# sGPSDO_MCU_1V0.net
KiCad netlist of a schematic drawn in EAGLE
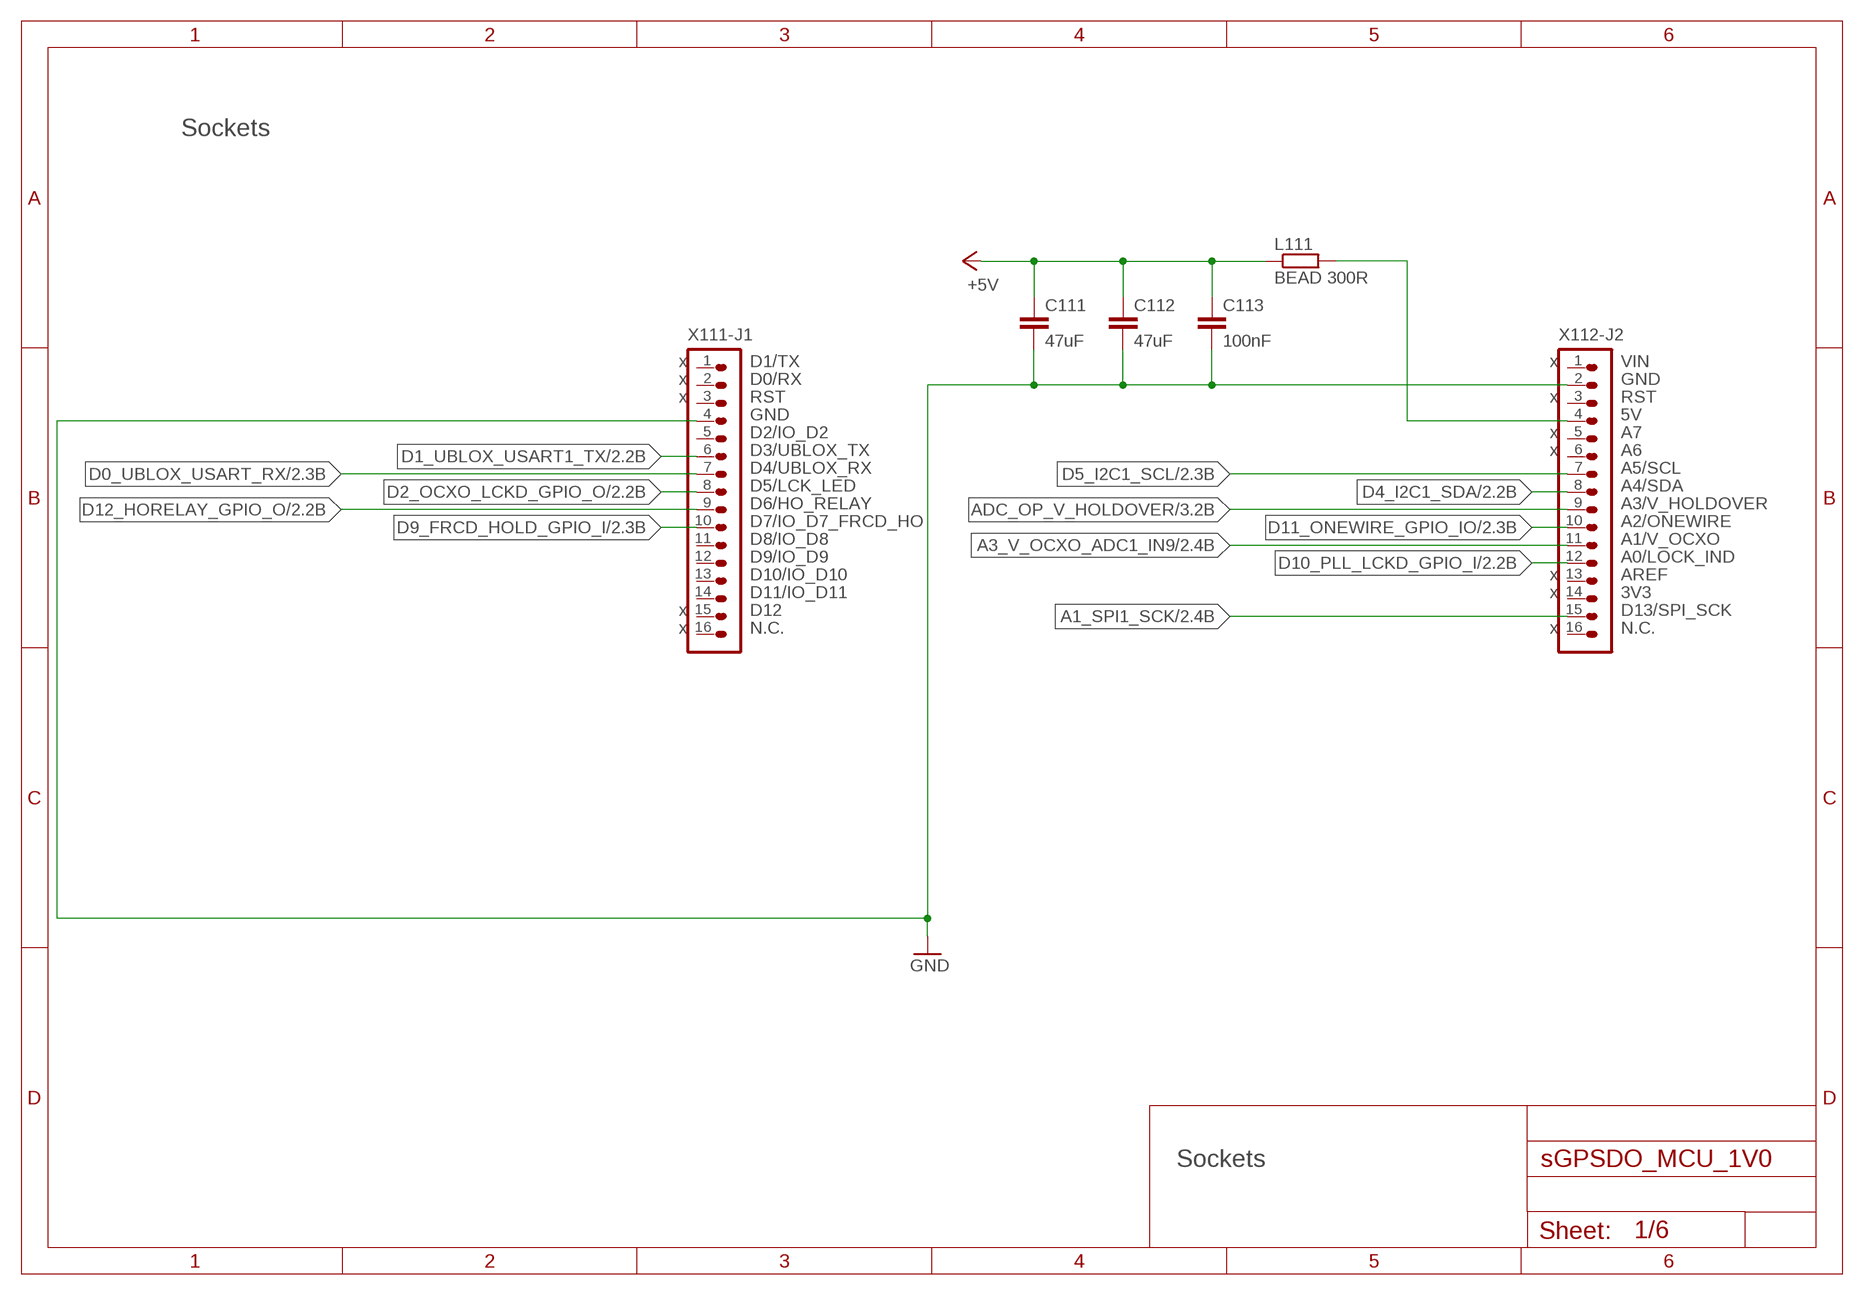
[diagram p0: schematic, sheet 1]
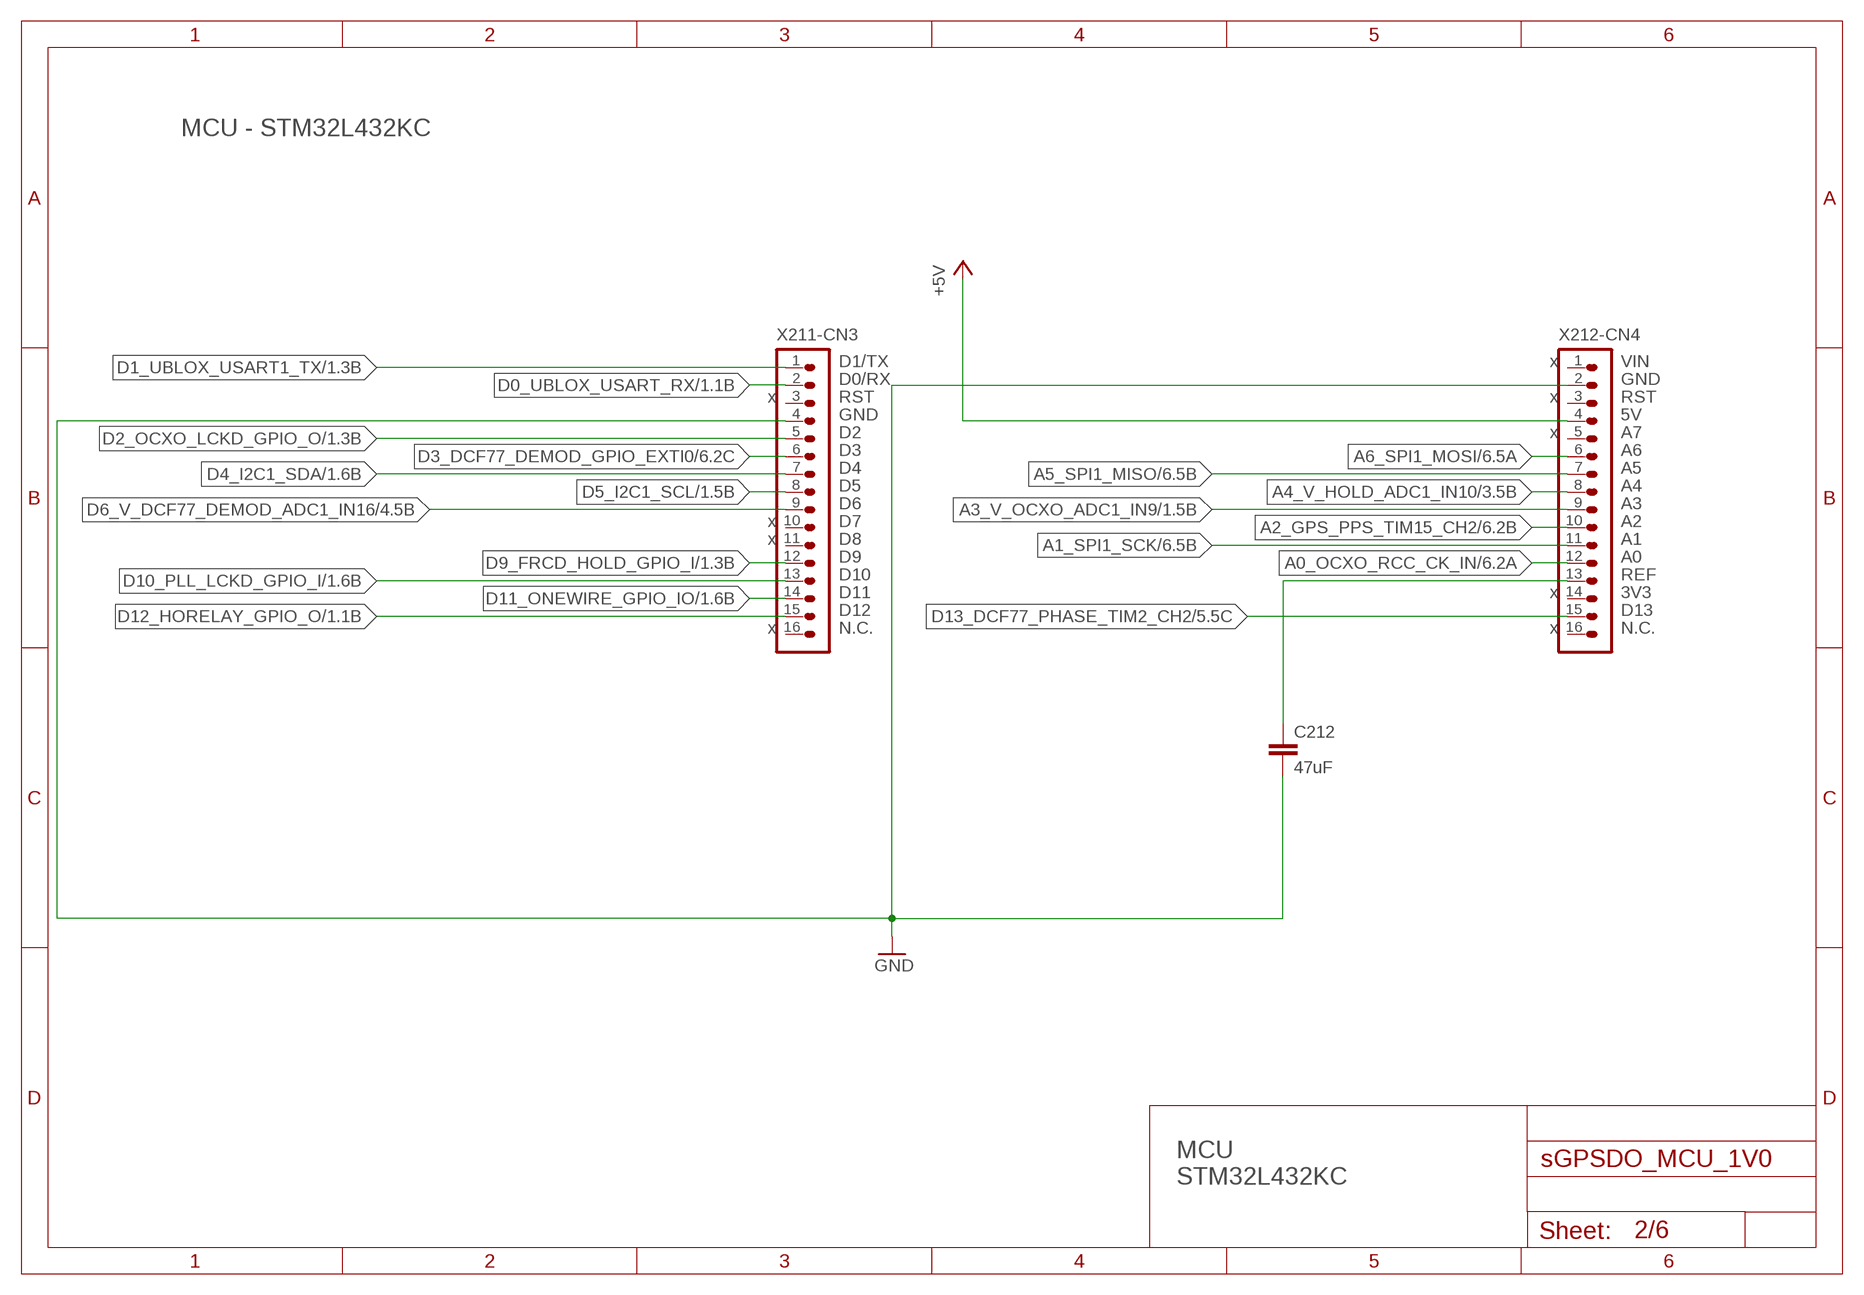
[diagram p1: schematic, sheet 2]
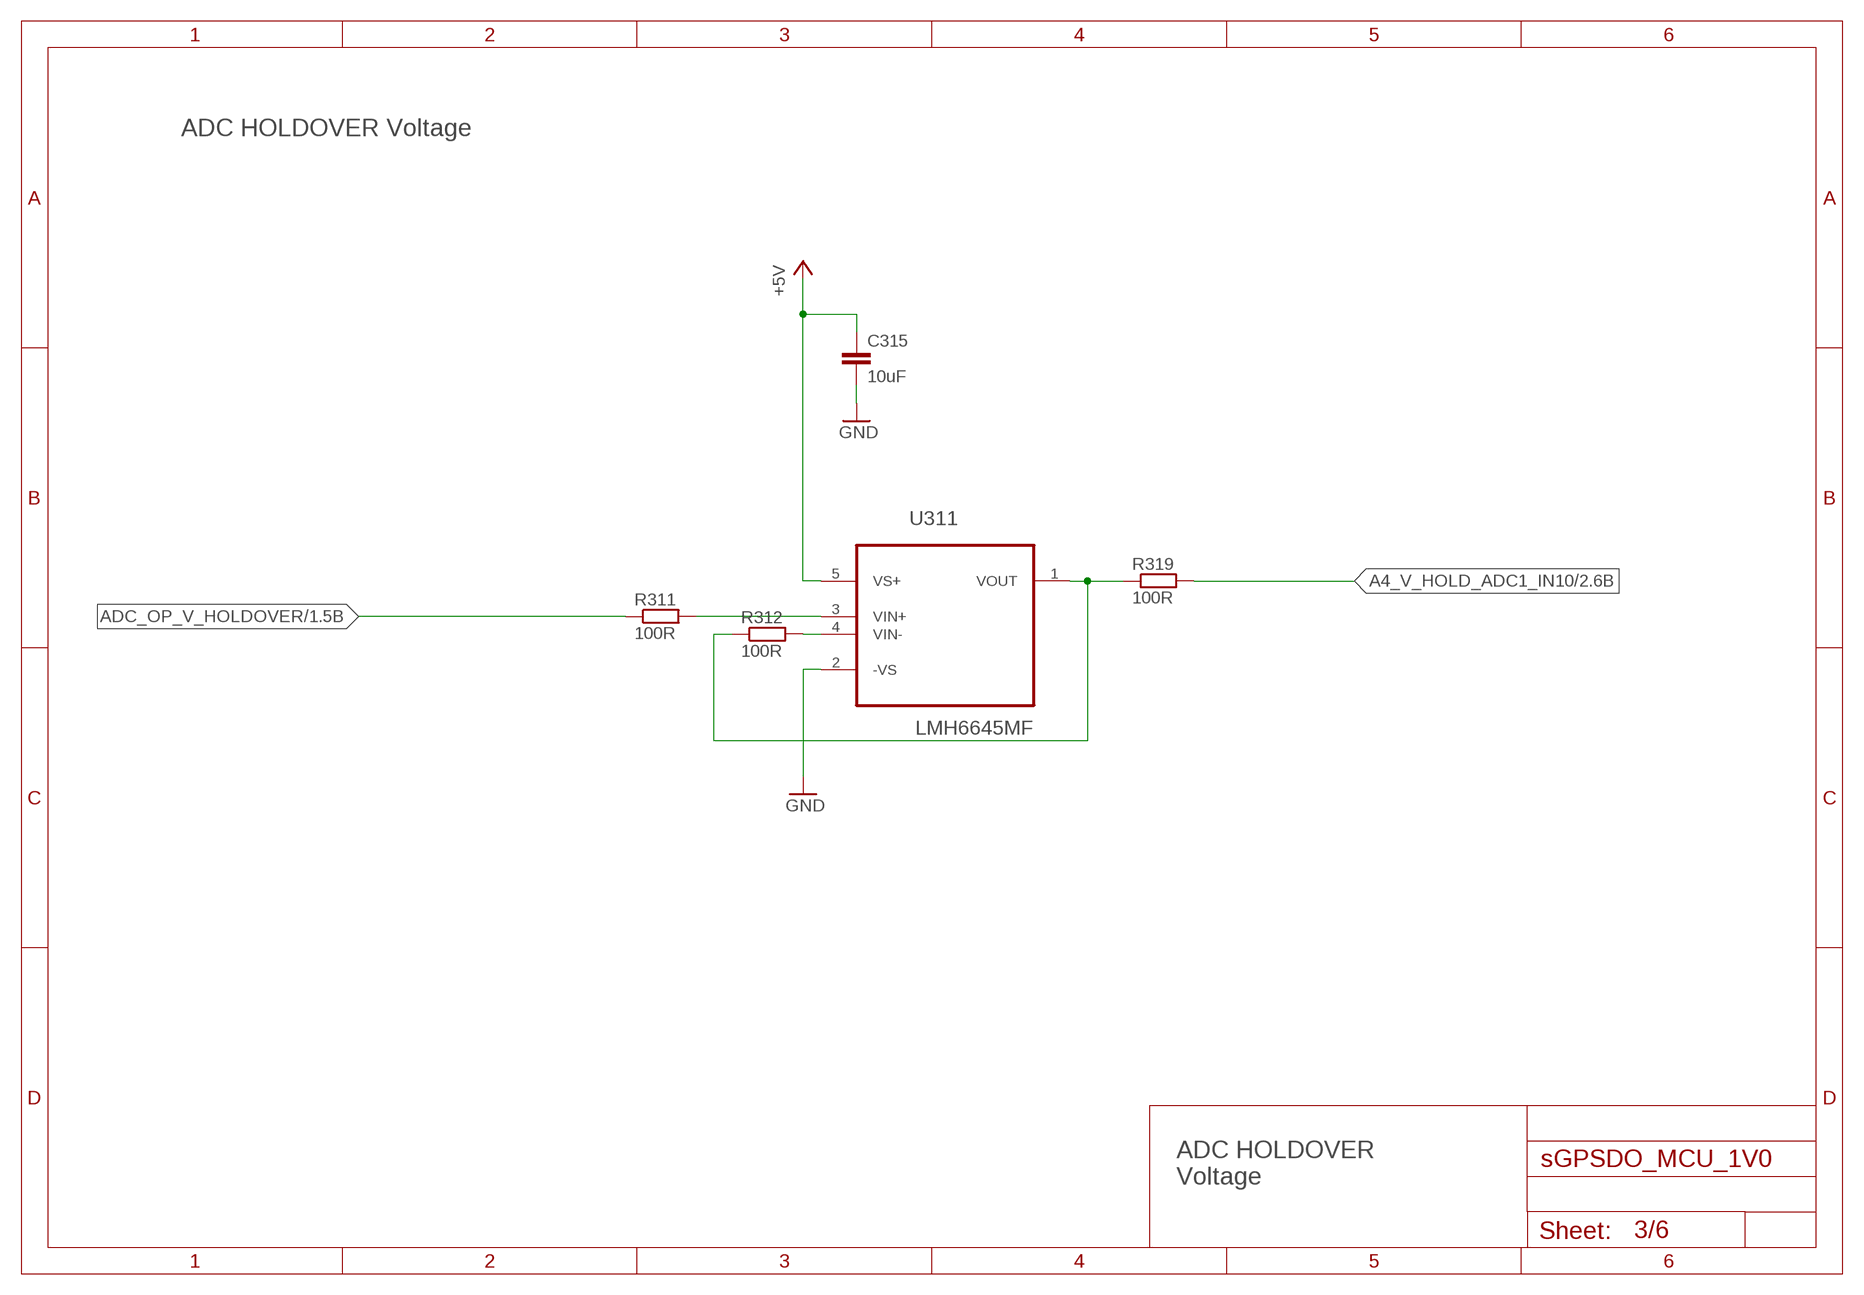
[diagram p2: schematic, sheet 3]
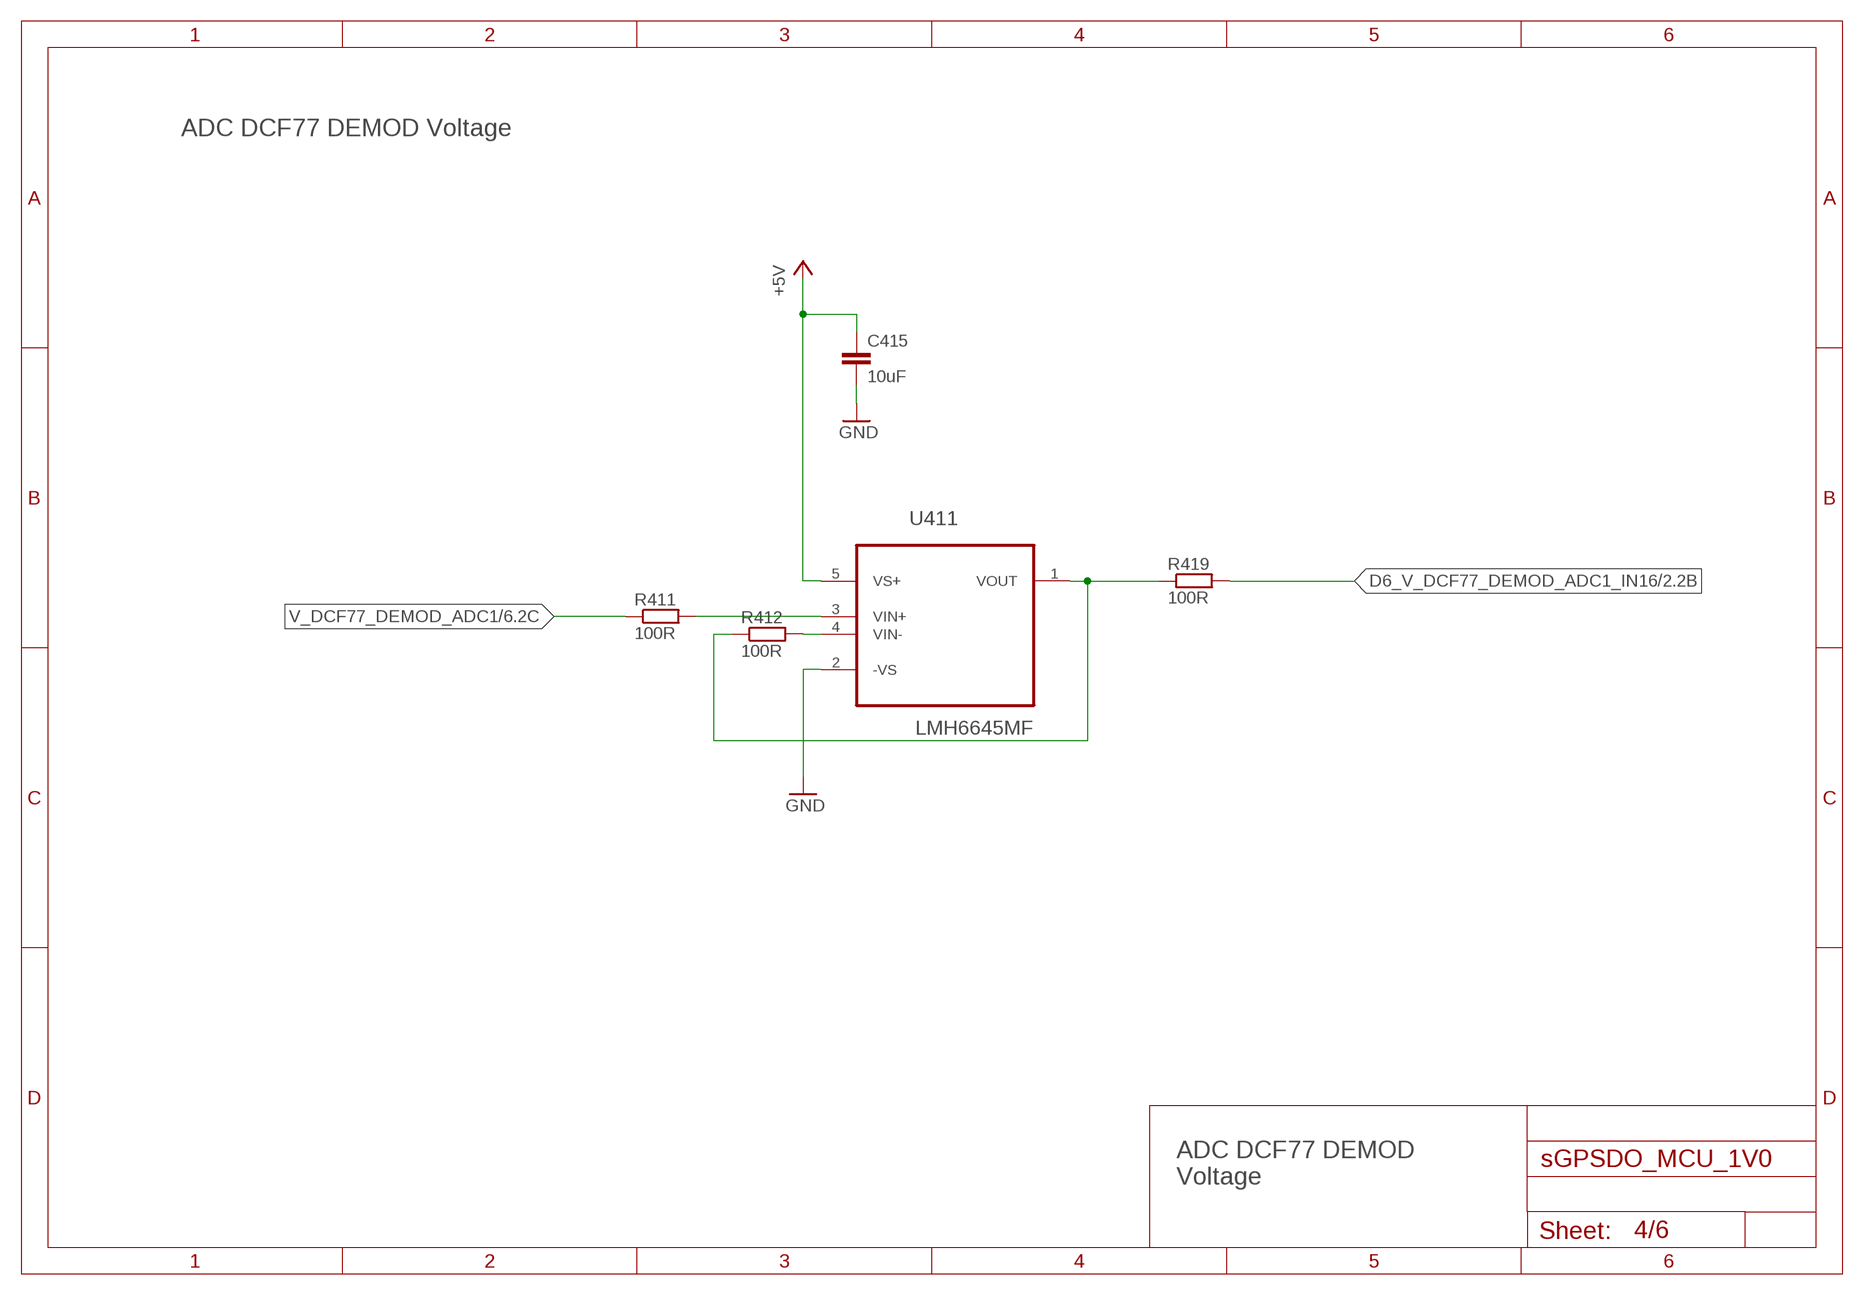
[diagram p3: schematic, sheet 4]
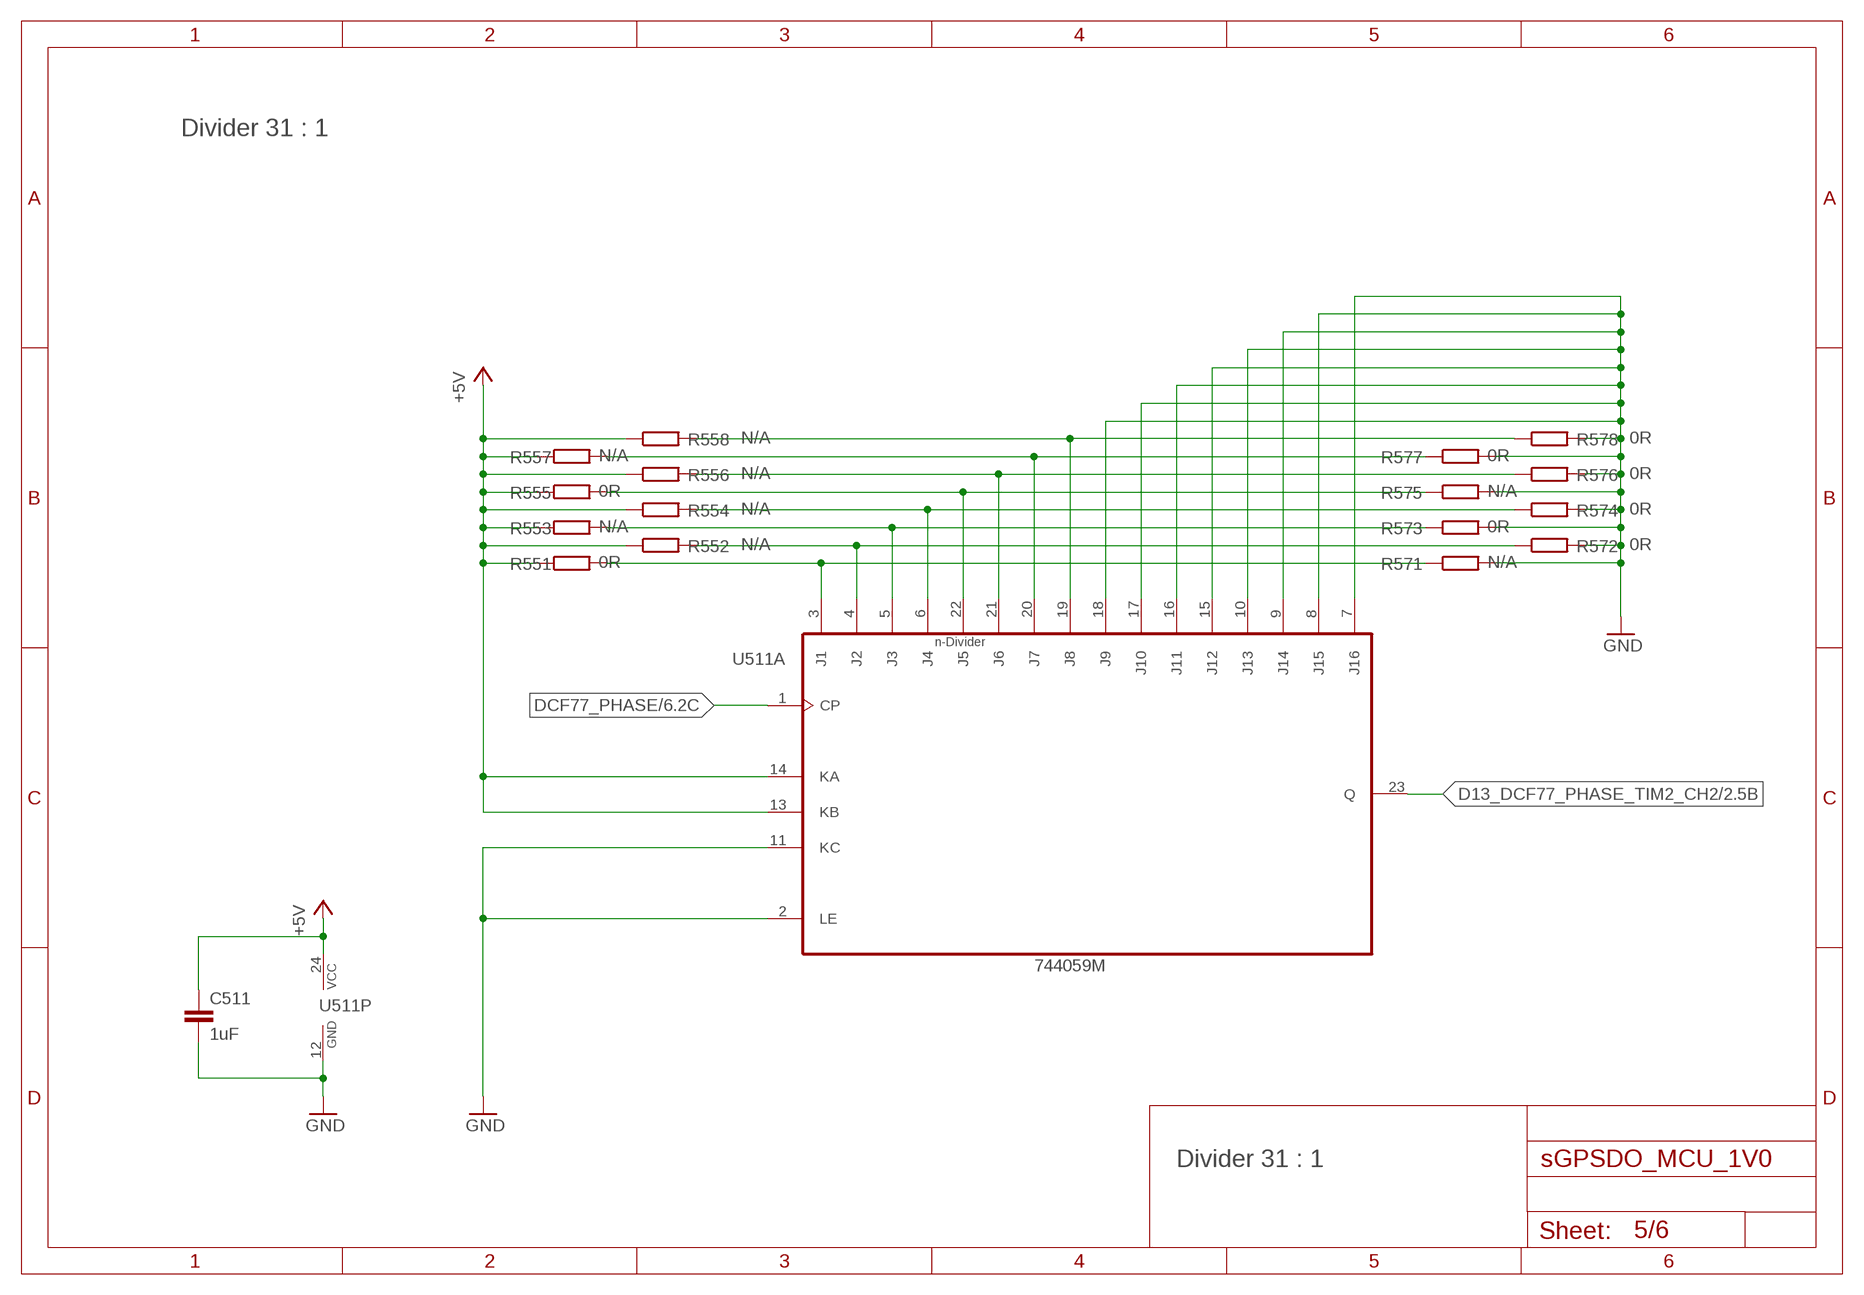
[diagram p4: schematic, sheet 5]
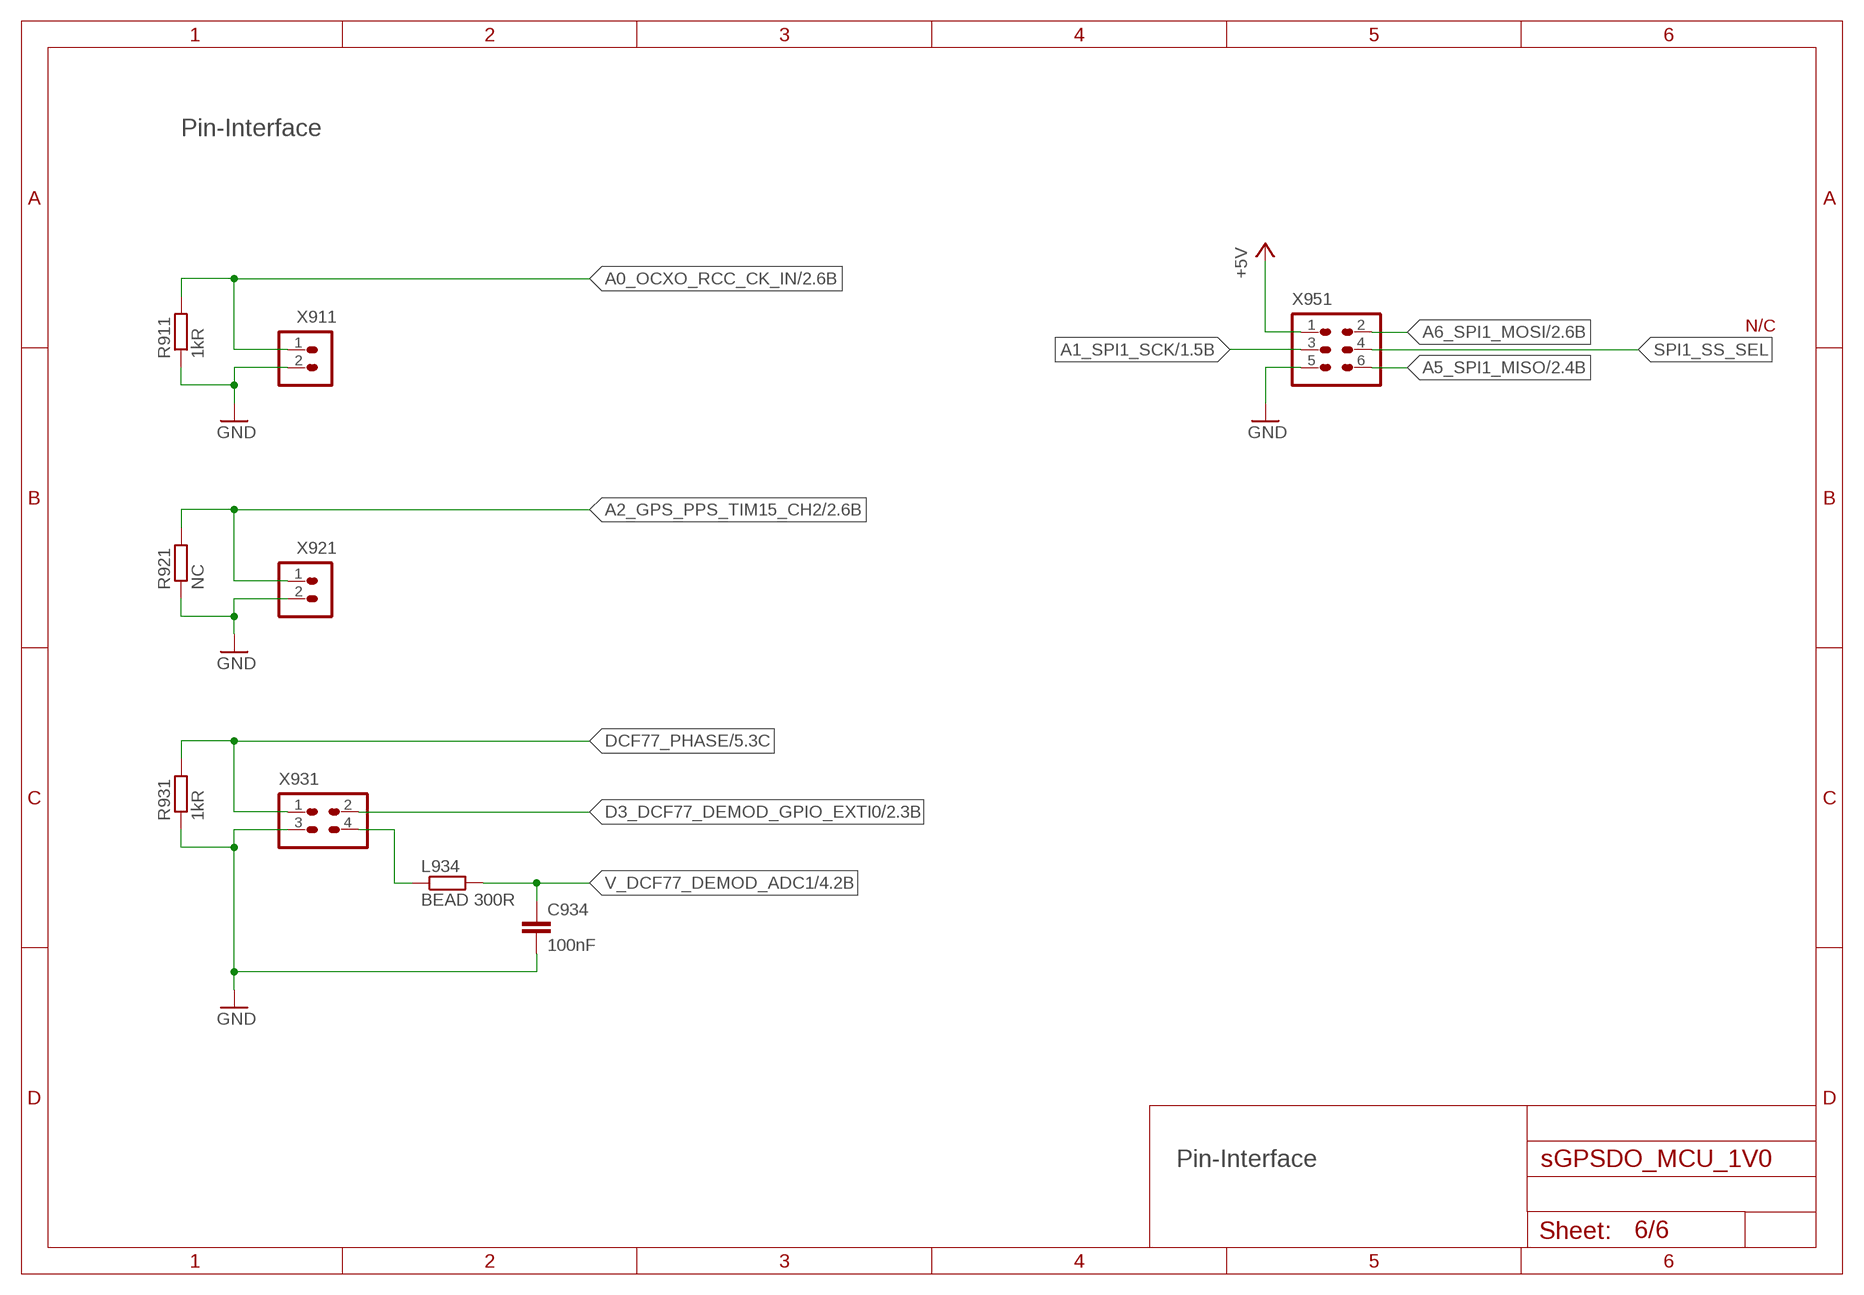
[diagram p5: schematic, sheet 6]

(export (version "E")
  (design (tool "Eeschema 10.0.6"))
  (components
    (comp (ref "C315")
      (value "10uF")
      (footprint "eagle-import:C0805")
      (libsource (lib "eagle-import") (part "C-EUC0805"))
    )
    (comp (ref "R311")
      (value "100R")
      (footprint "eagle-import:R0805")
      (libsource (lib "eagle-import") (part "R-EU_R0805"))
    )
    (comp (ref "R312")
      (value "100R")
      (footprint "eagle-import:R0805")
      (libsource (lib "eagle-import") (part "R-EU_R0805"))
    )
    (comp (ref "R319")
      (value "100R")
      (footprint "eagle-import:R0805")
      (libsource (lib "eagle-import") (part "R-EU_R0805"))
    )
    (comp (ref "U311")
      (value "LMH6645MF")
      (footprint "eagle-import:SOT-23-5")
      (libsource (lib "eagle-import") (part "LMH6645MF"))
    )
    (comp (ref "C511")
      (value "1uF")
      (footprint "eagle-import:C0805")
      (libsource (lib "eagle-import") (part "C-EUC0805"))
    )
    (comp (ref "R551")
      (value "0R")
      (footprint "eagle-import:R0402")
      (libsource (lib "eagle-import") (part "R-EU_R0402"))
    )
    (comp (ref "R552")
      (value "N/A")
      (footprint "eagle-import:R0402")
      (libsource (lib "eagle-import") (part "R-EU_R0402"))
    )
    (comp (ref "R553")
      (value "N/A")
      (footprint "eagle-import:R0402")
      (libsource (lib "eagle-import") (part "R-EU_R0402"))
    )
    (comp (ref "R554")
      (value "N/A")
      (footprint "eagle-import:R0402")
      (libsource (lib "eagle-import") (part "R-EU_R0402"))
    )
    (comp (ref "R555")
      (value "0R")
      (footprint "eagle-import:R0402")
      (libsource (lib "eagle-import") (part "R-EU_R0402"))
    )
    (comp (ref "R556")
      (value "N/A")
      (footprint "eagle-import:R0402")
      (libsource (lib "eagle-import") (part "R-EU_R0402"))
    )
    (comp (ref "R557")
      (value "N/A")
      (footprint "eagle-import:R0402")
      (libsource (lib "eagle-import") (part "R-EU_R0402"))
    )
    (comp (ref "R558")
      (value "N/A")
      (footprint "eagle-import:R0402")
      (libsource (lib "eagle-import") (part "R-EU_R0402"))
    )
    (comp (ref "R571")
      (value "N/A")
      (footprint "eagle-import:R0402")
      (libsource (lib "eagle-import") (part "R-EU_R0402"))
    )
    (comp (ref "R572")
      (value "0R")
      (footprint "eagle-import:R0402")
      (libsource (lib "eagle-import") (part "R-EU_R0402"))
    )
    (comp (ref "R573")
      (value "0R")
      (footprint "eagle-import:R0402")
      (libsource (lib "eagle-import") (part "R-EU_R0402"))
    )
    (comp (ref "R574")
      (value "0R")
      (footprint "eagle-import:R0402")
      (libsource (lib "eagle-import") (part "R-EU_R0402"))
    )
    (comp (ref "R575")
      (value "N/A")
      (footprint "eagle-import:R0402")
      (libsource (lib "eagle-import") (part "R-EU_R0402"))
    )
    (comp (ref "R576")
      (value "0R")
      (footprint "eagle-import:R0402")
      (libsource (lib "eagle-import") (part "R-EU_R0402"))
    )
    (comp (ref "R577")
      (value "0R")
      (footprint "eagle-import:R0402")
      (libsource (lib "eagle-import") (part "R-EU_R0402"))
    )
    (comp (ref "R578")
      (value "0R")
      (footprint "eagle-import:R0402")
      (libsource (lib "eagle-import") (part "R-EU_R0402"))
    )
    (comp (ref "U511")
      (value "744059M")
      (footprint "eagle-import:SO24")
      (libsource (lib "eagle-import") (part "744059M"))
    )
    (comp (ref "C111")
      (value "47uF")
      (footprint "eagle-import:C0805")
      (libsource (lib "eagle-import") (part "C-EUC0805"))
    )
    (comp (ref "C112")
      (value "47uF")
      (footprint "eagle-import:C0805")
      (libsource (lib "eagle-import") (part "C-EUC0805"))
    )
    (comp (ref "C113")
      (value "100nF")
      (footprint "eagle-import:C0805")
      (libsource (lib "eagle-import") (part "C-EUC0805"))
    )
    (comp (ref "L111")
      (value "BEAD 300R")
      (footprint "eagle-import:R1206")
      (libsource (lib "eagle-import") (part "R-EU_R1206"))
    )
    (comp (ref "X111-J1")
      (value "HEADER-1X16")
      (footprint "eagle-import:1X16")
      (libsource (lib "eagle-import") (part "HEADER-1X16"))
    )
    (comp (ref "X112-J2")
      (value "HEADER-1X16")
      (footprint "eagle-import:1X16")
      (libsource (lib "eagle-import") (part "HEADER-1X16"))
    )
    (comp (ref "C212")
      (value "47uF")
      (footprint "eagle-import:C0805")
      (libsource (lib "eagle-import") (part "C-EUC0805"))
    )
    (comp (ref "X211-CN3")
      (value "HEADER-1X16")
      (footprint "eagle-import:1X16")
      (libsource (lib "eagle-import") (part "HEADER-1X16"))
    )
    (comp (ref "X212-CN4")
      (value "HEADER-1X16")
      (footprint "eagle-import:1X16")
      (libsource (lib "eagle-import") (part "HEADER-1X16"))
    )
    (comp (ref "C934")
      (value "100nF")
      (footprint "eagle-import:C0805")
      (libsource (lib "eagle-import") (part "C-EUC0805"))
    )
    (comp (ref "L934")
      (value "BEAD 300R")
      (footprint "eagle-import:R1206")
      (libsource (lib "eagle-import") (part "R-EU_R1206"))
    )
    (comp (ref "R911")
      (value "1kR")
      (footprint "eagle-import:R0805")
      (libsource (lib "eagle-import") (part "R-EU_R0805"))
    )
    (comp (ref "R921")
      (value "NC")
      (footprint "eagle-import:R0805")
      (libsource (lib "eagle-import") (part "R-EU_R0805"))
    )
    (comp (ref "R931")
      (value "1kR")
      (footprint "eagle-import:R0805")
      (libsource (lib "eagle-import") (part "R-EU_R0805"))
    )
    (comp (ref "X911")
      (value "HEADER-1X2")
      (footprint "eagle-import:1X02")
      (libsource (lib "eagle-import") (part "HEADER-1X2"))
    )
    (comp (ref "X921")
      (value "HEADER-1X2")
      (footprint "eagle-import:1X02")
      (libsource (lib "eagle-import") (part "HEADER-1X2"))
    )
    (comp (ref "X931")
      (value "HEADER-2X2")
      (footprint "eagle-import:2X02")
      (libsource (lib "eagle-import") (part "HEADER-2X2"))
    )
    (comp (ref "X951")
      (value "HEADER-2X3")
      (footprint "eagle-import:2X03")
      (libsource (lib "eagle-import") (part "HEADER-2X3"))
    )
    (comp (ref "C415")
      (value "10uF")
      (footprint "eagle-import:C0805")
      (libsource (lib "eagle-import") (part "C-EUC0805"))
    )
    (comp (ref "R411")
      (value "100R")
      (footprint "eagle-import:R0805")
      (libsource (lib "eagle-import") (part "R-EU_R0805"))
    )
    (comp (ref "R412")
      (value "100R")
      (footprint "eagle-import:R0805")
      (libsource (lib "eagle-import") (part "R-EU_R0805"))
    )
    (comp (ref "R419")
      (value "100R")
      (footprint "eagle-import:R0805")
      (libsource (lib "eagle-import") (part "R-EU_R0805"))
    )
    (comp (ref "U411")
      (value "LMH6645MF")
      (footprint "eagle-import:SOT-23-5")
      (libsource (lib "eagle-import") (part "LMH6645MF"))
    )
  )
  (nets
    (net (code "1") (name "+5V") (class "Default")
      (node (ref "C111") (pin "1") (pinfunction "1_1") (pintype "passive"))
      (node (ref "C112") (pin "1") (pinfunction "1_1") (pintype "passive"))
      (node (ref "C113") (pin "1") (pinfunction "1_1") (pintype "passive"))
      (node (ref "C315") (pin "1") (pinfunction "1_1") (pintype "passive"))
      (node (ref "C415") (pin "1") (pinfunction "1_1") (pintype "passive"))
      (node (ref "C511") (pin "1") (pinfunction "1_1") (pintype "passive"))
      (node (ref "L111") (pin "1") (pinfunction "1_1") (pintype "passive"))
      (node (ref "R551") (pin "1") (pinfunction "1_1") (pintype "passive"))
      (node (ref "R552") (pin "1") (pinfunction "1_1") (pintype "passive"))
      (node (ref "R553") (pin "1") (pinfunction "1_1") (pintype "passive"))
      (node (ref "R554") (pin "1") (pinfunction "1_1") (pintype "passive"))
      (node (ref "R555") (pin "1") (pinfunction "1_1") (pintype "passive"))
      (node (ref "R556") (pin "1") (pinfunction "1_1") (pintype "passive"))
      (node (ref "R557") (pin "1") (pinfunction "1_1") (pintype "passive"))
      (node (ref "R558") (pin "1") (pinfunction "1_1") (pintype "passive"))
      (node (ref "U311") (pin "5") (pinfunction "VS+_5") (pintype "power_in"))
      (node (ref "U411") (pin "5") (pinfunction "VS+_5") (pintype "power_in"))
      (node (ref "U511") (pin "13") (pinfunction "KB_13") (pintype "input"))
      (node (ref "U511") (pin "14") (pinfunction "KA_14") (pintype "input"))
      (node (ref "U511") (pin "24") (pinfunction "VCC_24") (pintype "power_in"))
      (node (ref "X212-CN4") (pin "4") (pinfunction "4_4") (pintype "passive"))
      (node (ref "X951") (pin "1") (pinfunction "1_1") (pintype "passive"))
    )
    (net (code "2") (name "A0_OCXO_RCC_CK_IN") (class "Default")
      (node (ref "R911") (pin "2") (pinfunction "2_2") (pintype "passive"))
      (node (ref "X212-CN4") (pin "12") (pinfunction "12_12") (pintype "passive"))
      (node (ref "X911") (pin "1") (pinfunction "1_1") (pintype "passive"))
    )
    (net (code "3") (name "A1_SPI1_SCK") (class "Default")
      (node (ref "X112-J2") (pin "15") (pinfunction "15_15") (pintype "passive"))
      (node (ref "X212-CN4") (pin "11") (pinfunction "11_11") (pintype "passive"))
      (node (ref "X951") (pin "3") (pinfunction "3_3") (pintype "passive"))
    )
    (net (code "4") (name "A2_GPS_PPS_TIM15_CH2") (class "Default")
      (node (ref "R921") (pin "2") (pinfunction "2_2") (pintype "passive"))
      (node (ref "X212-CN4") (pin "10") (pinfunction "10_10") (pintype "passive"))
      (node (ref "X921") (pin "1") (pinfunction "1_1") (pintype "passive"))
    )
    (net (code "5") (name "A3_V_OCXO_ADC1_IN9") (class "Default")
      (node (ref "X112-J2") (pin "11") (pinfunction "11_11") (pintype "passive"))
      (node (ref "X212-CN4") (pin "9") (pinfunction "9_9") (pintype "passive"))
    )
    (net (code "6") (name "A4_V_HOLD_ADC1_IN10") (class "Default")
      (node (ref "R319") (pin "2") (pinfunction "2_2") (pintype "passive"))
      (node (ref "X212-CN4") (pin "8") (pinfunction "8_8") (pintype "passive"))
    )
    (net (code "7") (name "A5_SPI1_MISO") (class "Default")
      (node (ref "X212-CN4") (pin "7") (pinfunction "7_7") (pintype "passive"))
      (node (ref "X951") (pin "6") (pinfunction "6_6") (pintype "passive"))
    )
    (net (code "8") (name "A6_SPI1_MOSI") (class "Default")
      (node (ref "X212-CN4") (pin "6") (pinfunction "6_6") (pintype "passive"))
      (node (ref "X951") (pin "2") (pinfunction "2_2") (pintype "passive"))
    )
    (net (code "9") (name "ADC_OP_V_HOLDOVER") (class "Default")
      (node (ref "R311") (pin "1") (pinfunction "1_1") (pintype "passive"))
      (node (ref "X112-J2") (pin "9") (pinfunction "9_9") (pintype "passive"))
    )
    (net (code "10") (name "D0_UBLOX_USART_RX") (class "Default")
      (node (ref "X111-J1") (pin "7") (pinfunction "7_7") (pintype "passive"))
      (node (ref "X211-CN3") (pin "2") (pinfunction "2_2") (pintype "passive"))
    )
    (net (code "11") (name "D1_UBLOX_USART1_TX") (class "Default")
      (node (ref "X111-J1") (pin "6") (pinfunction "6_6") (pintype "passive"))
      (node (ref "X211-CN3") (pin "1") (pinfunction "1_1") (pintype "passive"))
    )
    (net (code "12") (name "D2_OCXO_LCKD_GPIO_O") (class "Default")
      (node (ref "X111-J1") (pin "8") (pinfunction "8_8") (pintype "passive"))
      (node (ref "X211-CN3") (pin "5") (pinfunction "5_5") (pintype "passive"))
    )
    (net (code "13") (name "D3_DCF77_DEMOD_GPIO_EXTI0") (class "Default")
      (node (ref "X211-CN3") (pin "6") (pinfunction "6_6") (pintype "passive"))
      (node (ref "X931") (pin "2") (pinfunction "2_2") (pintype "passive"))
    )
    (net (code "14") (name "D4_I2C1_SDA") (class "Default")
      (node (ref "X112-J2") (pin "8") (pinfunction "8_8") (pintype "passive"))
      (node (ref "X211-CN3") (pin "7") (pinfunction "7_7") (pintype "passive"))
    )
    (net (code "15") (name "D5_I2C1_SCL") (class "Default")
      (node (ref "X112-J2") (pin "7") (pinfunction "7_7") (pintype "passive"))
      (node (ref "X211-CN3") (pin "8") (pinfunction "8_8") (pintype "passive"))
    )
    (net (code "16") (name "D6_V_DCF77_DEMOD_ADC1_IN16") (class "Default")
      (node (ref "R419") (pin "2") (pinfunction "2_2") (pintype "passive"))
      (node (ref "X211-CN3") (pin "9") (pinfunction "9_9") (pintype "passive"))
    )
    (net (code "17") (name "D9_FRCD_HOLD_GPIO_I") (class "Default")
      (node (ref "X111-J1") (pin "10") (pinfunction "10_10") (pintype "passive"))
      (node (ref "X211-CN3") (pin "12") (pinfunction "12_12") (pintype "passive"))
    )
    (net (code "18") (name "D10_PLL_LCKD_GPIO_I") (class "Default")
      (node (ref "X112-J2") (pin "12") (pinfunction "12_12") (pintype "passive"))
      (node (ref "X211-CN3") (pin "13") (pinfunction "13_13") (pintype "passive"))
    )
    (net (code "19") (name "D11_ONEWIRE_GPIO_IO") (class "Default")
      (node (ref "X112-J2") (pin "10") (pinfunction "10_10") (pintype "passive"))
      (node (ref "X211-CN3") (pin "14") (pinfunction "14_14") (pintype "passive"))
    )
    (net (code "20") (name "D12_HORELAY_GPIO_O") (class "Default")
      (node (ref "X111-J1") (pin "9") (pinfunction "9_9") (pintype "passive"))
      (node (ref "X211-CN3") (pin "15") (pinfunction "15_15") (pintype "passive"))
    )
    (net (code "21") (name "D13_DCF77_PHASE_TIM2_CH2") (class "Default")
      (node (ref "U511") (pin "23") (pinfunction "Q_23") (pintype "output"))
      (node (ref "X212-CN4") (pin "15") (pinfunction "15_15") (pintype "passive"))
    )
    (net (code "22") (name "DCF77_PHASE") (class "Default")
      (node (ref "R931") (pin "2") (pinfunction "2_2") (pintype "passive"))
      (node (ref "U511") (pin "1") (pinfunction "CP_1") (pintype "input"))
      (node (ref "X931") (pin "1") (pinfunction "1_1") (pintype "passive"))
    )
    (net (code "23") (name "GND") (class "Default")
      (node (ref "C111") (pin "2") (pinfunction "2_2") (pintype "passive"))
      (node (ref "C112") (pin "2") (pinfunction "2_2") (pintype "passive"))
      (node (ref "C113") (pin "2") (pinfunction "2_2") (pintype "passive"))
      (node (ref "C212") (pin "2") (pinfunction "2_2") (pintype "passive"))
      (node (ref "C315") (pin "2") (pinfunction "2_2") (pintype "passive"))
      (node (ref "C415") (pin "2") (pinfunction "2_2") (pintype "passive"))
      (node (ref "C511") (pin "2") (pinfunction "2_2") (pintype "passive"))
      (node (ref "C934") (pin "2") (pinfunction "2_2") (pintype "passive"))
      (node (ref "R571") (pin "2") (pinfunction "2_2") (pintype "passive"))
      (node (ref "R572") (pin "2") (pinfunction "2_2") (pintype "passive"))
      (node (ref "R573") (pin "2") (pinfunction "2_2") (pintype "passive"))
      (node (ref "R574") (pin "2") (pinfunction "2_2") (pintype "passive"))
      (node (ref "R575") (pin "2") (pinfunction "2_2") (pintype "passive"))
      (node (ref "R576") (pin "2") (pinfunction "2_2") (pintype "passive"))
      (node (ref "R577") (pin "2") (pinfunction "2_2") (pintype "passive"))
      (node (ref "R578") (pin "2") (pinfunction "2_2") (pintype "passive"))
      (node (ref "R911") (pin "1") (pinfunction "1_1") (pintype "passive"))
      (node (ref "R921") (pin "1") (pinfunction "1_1") (pintype "passive"))
      (node (ref "R931") (pin "1") (pinfunction "1_1") (pintype "passive"))
      (node (ref "U311") (pin "2") (pinfunction "-VS_2") (pintype "power_in"))
      (node (ref "U411") (pin "2") (pinfunction "-VS_2") (pintype "power_in"))
      (node (ref "U511") (pin "10") (pinfunction "J13_10") (pintype "input"))
      (node (ref "U511") (pin "11") (pinfunction "KC_11") (pintype "input"))
      (node (ref "U511") (pin "12") (pinfunction "GND_12") (pintype "power_in"))
      (node (ref "U511") (pin "15") (pinfunction "J12_15") (pintype "input"))
      (node (ref "U511") (pin "16") (pinfunction "J11_16") (pintype "input"))
      (node (ref "U511") (pin "17") (pinfunction "J10_17") (pintype "input"))
      (node (ref "U511") (pin "18") (pinfunction "J9_18") (pintype "input"))
      (node (ref "U511") (pin "2") (pinfunction "LE_2") (pintype "input"))
      (node (ref "U511") (pin "7") (pinfunction "J16_7") (pintype "input"))
      (node (ref "U511") (pin "8") (pinfunction "J15_8") (pintype "input"))
      (node (ref "U511") (pin "9") (pinfunction "J14_9") (pintype "input"))
      (node (ref "X111-J1") (pin "4") (pinfunction "4_4") (pintype "passive"))
      (node (ref "X112-J2") (pin "2") (pinfunction "2_2") (pintype "passive"))
      (node (ref "X211-CN3") (pin "4") (pinfunction "4_4") (pintype "passive"))
      (node (ref "X212-CN4") (pin "2") (pinfunction "2_2") (pintype "passive"))
      (node (ref "X911") (pin "2") (pinfunction "2_2") (pintype "passive"))
      (node (ref "X921") (pin "2") (pinfunction "2_2") (pintype "passive"))
      (node (ref "X931") (pin "3") (pinfunction "3_3") (pintype "passive"))
      (node (ref "X951") (pin "5") (pinfunction "5_5") (pintype "passive"))
    )
    (net (code "24") (name "Net-(C212-Pad1)") (class "Default")
      (node (ref "C212") (pin "1") (pinfunction "1_1") (pintype "passive"))
      (node (ref "X212-CN4") (pin "13") (pinfunction "13_13") (pintype "passive"))
    )
    (net (code "25") (name "Net-(L111-Pad2)") (class "Default")
      (node (ref "L111") (pin "2") (pinfunction "2_2") (pintype "passive"))
      (node (ref "X112-J2") (pin "4") (pinfunction "4_4") (pintype "passive"))
    )
    (net (code "26") (name "Net-(L934-Pad1)") (class "Default")
      (node (ref "L934") (pin "1") (pinfunction "1_1") (pintype "passive"))
      (node (ref "X931") (pin "4") (pinfunction "4_4") (pintype "passive"))
    )
    (net (code "27") (name "Net-(U311-VIN+)") (class "Default")
      (node (ref "R311") (pin "2") (pinfunction "2_2") (pintype "passive"))
      (node (ref "U311") (pin "3") (pinfunction "VIN+_3") (pintype "input"))
    )
    (net (code "28") (name "Net-(U311-VIN-)") (class "Default")
      (node (ref "R312") (pin "2") (pinfunction "2_2") (pintype "passive"))
      (node (ref "U311") (pin "4") (pinfunction "VIN-_4") (pintype "input"))
    )
    (net (code "29") (name "Net-(U311-VOUT)") (class "Default")
      (node (ref "R312") (pin "1") (pinfunction "1_1") (pintype "passive"))
      (node (ref "R319") (pin "1") (pinfunction "1_1") (pintype "passive"))
      (node (ref "U311") (pin "1") (pinfunction "VOUT_1") (pintype "output"))
    )
    (net (code "30") (name "Net-(U411-VIN+)") (class "Default")
      (node (ref "R411") (pin "2") (pinfunction "2_2") (pintype "passive"))
      (node (ref "U411") (pin "3") (pinfunction "VIN+_3") (pintype "input"))
    )
    (net (code "31") (name "Net-(U411-VIN-)") (class "Default")
      (node (ref "R412") (pin "2") (pinfunction "2_2") (pintype "passive"))
      (node (ref "U411") (pin "4") (pinfunction "VIN-_4") (pintype "input"))
    )
    (net (code "32") (name "Net-(U411-VOUT)") (class "Default")
      (node (ref "R412") (pin "1") (pinfunction "1_1") (pintype "passive"))
      (node (ref "R419") (pin "1") (pinfunction "1_1") (pintype "passive"))
      (node (ref "U411") (pin "1") (pinfunction "VOUT_1") (pintype "output"))
    )
    (net (code "33") (name "Net-(U511A-J1)") (class "Default")
      (node (ref "R551") (pin "2") (pinfunction "2_2") (pintype "passive"))
      (node (ref "R571") (pin "1") (pinfunction "1_1") (pintype "passive"))
      (node (ref "U511") (pin "3") (pinfunction "J1_3") (pintype "input"))
    )
    (net (code "34") (name "Net-(U511A-J2)") (class "Default")
      (node (ref "R552") (pin "2") (pinfunction "2_2") (pintype "passive"))
      (node (ref "R572") (pin "1") (pinfunction "1_1") (pintype "passive"))
      (node (ref "U511") (pin "4") (pinfunction "J2_4") (pintype "input"))
    )
    (net (code "35") (name "Net-(U511A-J3)") (class "Default")
      (node (ref "R553") (pin "2") (pinfunction "2_2") (pintype "passive"))
      (node (ref "R573") (pin "1") (pinfunction "1_1") (pintype "passive"))
      (node (ref "U511") (pin "5") (pinfunction "J3_5") (pintype "input"))
    )
    (net (code "36") (name "Net-(U511A-J4)") (class "Default")
      (node (ref "R554") (pin "2") (pinfunction "2_2") (pintype "passive"))
      (node (ref "R574") (pin "1") (pinfunction "1_1") (pintype "passive"))
      (node (ref "U511") (pin "6") (pinfunction "J4_6") (pintype "input"))
    )
    (net (code "37") (name "Net-(U511A-J5)") (class "Default")
      (node (ref "R555") (pin "2") (pinfunction "2_2") (pintype "passive"))
      (node (ref "R575") (pin "1") (pinfunction "1_1") (pintype "passive"))
      (node (ref "U511") (pin "22") (pinfunction "J5_22") (pintype "input"))
    )
    (net (code "38") (name "Net-(U511A-J6)") (class "Default")
      (node (ref "R556") (pin "2") (pinfunction "2_2") (pintype "passive"))
      (node (ref "R576") (pin "1") (pinfunction "1_1") (pintype "passive"))
      (node (ref "U511") (pin "21") (pinfunction "J6_21") (pintype "input"))
    )
    (net (code "39") (name "Net-(U511A-J7)") (class "Default")
      (node (ref "R557") (pin "2") (pinfunction "2_2") (pintype "passive"))
      (node (ref "R577") (pin "1") (pinfunction "1_1") (pintype "passive"))
      (node (ref "U511") (pin "20") (pinfunction "J7_20") (pintype "input"))
    )
    (net (code "40") (name "Net-(U511A-J8)") (class "Default")
      (node (ref "R558") (pin "2") (pinfunction "2_2") (pintype "passive"))
      (node (ref "R578") (pin "1") (pinfunction "1_1") (pintype "passive"))
      (node (ref "U511") (pin "19") (pinfunction "J8_19") (pintype "input"))
    )
    (net (code "41") (name "SPI1_SS_SEL") (class "Default")
      (node (ref "X951") (pin "4") (pinfunction "4_4") (pintype "passive"))
    )
    (net (code "42") (name "V_DCF77_DEMOD_ADC1") (class "Default")
      (node (ref "C934") (pin "1") (pinfunction "1_1") (pintype "passive"))
      (node (ref "L934") (pin "2") (pinfunction "2_2") (pintype "passive"))
      (node (ref "R411") (pin "1") (pinfunction "1_1") (pintype "passive"))
    )
    (net (code "43") (name "unconnected-(X111-J1-Pad1)") (class "Default")
      (node (ref "X111-J1") (pin "1") (pinfunction "1_1") (pintype "passive"))
    )
    (net (code "44") (name "unconnected-(X111-J1-Pad2)") (class "Default")
      (node (ref "X111-J1") (pin "2") (pinfunction "2_2") (pintype "passive"))
    )
    (net (code "45") (name "unconnected-(X111-J1-Pad3)") (class "Default")
      (node (ref "X111-J1") (pin "3") (pinfunction "3_3") (pintype "passive"))
    )
    (net (code "46") (name "unconnected-(X111-J1-Pad5)") (class "Default")
      (node (ref "X111-J1") (pin "5") (pinfunction "5_5") (pintype "passive"))
    )
    (net (code "47") (name "unconnected-(X111-J1-Pad11)") (class "Default")
      (node (ref "X111-J1") (pin "11") (pinfunction "11_11") (pintype "passive"))
    )
    (net (code "48") (name "unconnected-(X111-J1-Pad12)") (class "Default")
      (node (ref "X111-J1") (pin "12") (pinfunction "12_12") (pintype "passive"))
    )
    (net (code "49") (name "unconnected-(X111-J1-Pad13)") (class "Default")
      (node (ref "X111-J1") (pin "13") (pinfunction "13_13") (pintype "passive"))
    )
    (net (code "50") (name "unconnected-(X111-J1-Pad14)") (class "Default")
      (node (ref "X111-J1") (pin "14") (pinfunction "14_14") (pintype "passive"))
    )
    (net (code "51") (name "unconnected-(X111-J1-Pad15)") (class "Default")
      (node (ref "X111-J1") (pin "15") (pinfunction "15_15") (pintype "passive"))
    )
    (net (code "52") (name "unconnected-(X111-J1-Pad16)") (class "Default")
      (node (ref "X111-J1") (pin "16") (pinfunction "16_16") (pintype "passive"))
    )
    (net (code "53") (name "unconnected-(X112-J2-Pad1)") (class "Default")
      (node (ref "X112-J2") (pin "1") (pinfunction "1_1") (pintype "passive"))
    )
    (net (code "54") (name "unconnected-(X112-J2-Pad3)") (class "Default")
      (node (ref "X112-J2") (pin "3") (pinfunction "3_3") (pintype "passive"))
    )
    (net (code "55") (name "unconnected-(X112-J2-Pad5)") (class "Default")
      (node (ref "X112-J2") (pin "5") (pinfunction "5_5") (pintype "passive"))
    )
    (net (code "56") (name "unconnected-(X112-J2-Pad6)") (class "Default")
      (node (ref "X112-J2") (pin "6") (pinfunction "6_6") (pintype "passive"))
    )
    (net (code "57") (name "unconnected-(X112-J2-Pad13)") (class "Default")
      (node (ref "X112-J2") (pin "13") (pinfunction "13_13") (pintype "passive"))
    )
    (net (code "58") (name "unconnected-(X112-J2-Pad14)") (class "Default")
      (node (ref "X112-J2") (pin "14") (pinfunction "14_14") (pintype "passive"))
    )
    (net (code "59") (name "unconnected-(X112-J2-Pad16)") (class "Default")
      (node (ref "X112-J2") (pin "16") (pinfunction "16_16") (pintype "passive"))
    )
    (net (code "60") (name "unconnected-(X211-CN3-Pad3)") (class "Default")
      (node (ref "X211-CN3") (pin "3") (pinfunction "3_3") (pintype "passive"))
    )
    (net (code "61") (name "unconnected-(X211-CN3-Pad10)") (class "Default")
      (node (ref "X211-CN3") (pin "10") (pinfunction "10_10") (pintype "passive"))
    )
    (net (code "62") (name "unconnected-(X211-CN3-Pad11)") (class "Default")
      (node (ref "X211-CN3") (pin "11") (pinfunction "11_11") (pintype "passive"))
    )
    (net (code "63") (name "unconnected-(X211-CN3-Pad16)") (class "Default")
      (node (ref "X211-CN3") (pin "16") (pinfunction "16_16") (pintype "passive"))
    )
    (net (code "64") (name "unconnected-(X212-CN4-Pad1)") (class "Default")
      (node (ref "X212-CN4") (pin "1") (pinfunction "1_1") (pintype "passive"))
    )
    (net (code "65") (name "unconnected-(X212-CN4-Pad3)") (class "Default")
      (node (ref "X212-CN4") (pin "3") (pinfunction "3_3") (pintype "passive"))
    )
    (net (code "66") (name "unconnected-(X212-CN4-Pad5)") (class "Default")
      (node (ref "X212-CN4") (pin "5") (pinfunction "5_5") (pintype "passive"))
    )
    (net (code "67") (name "unconnected-(X212-CN4-Pad14)") (class "Default")
      (node (ref "X212-CN4") (pin "14") (pinfunction "14_14") (pintype "passive"))
    )
    (net (code "68") (name "unconnected-(X212-CN4-Pad16)") (class "Default")
      (node (ref "X212-CN4") (pin "16") (pinfunction "16_16") (pintype "passive"))
    )
  )
)
